# 06-Front_Panel_SFP_2.net
KiCad netlist of a schematic drawn in Altium Designer
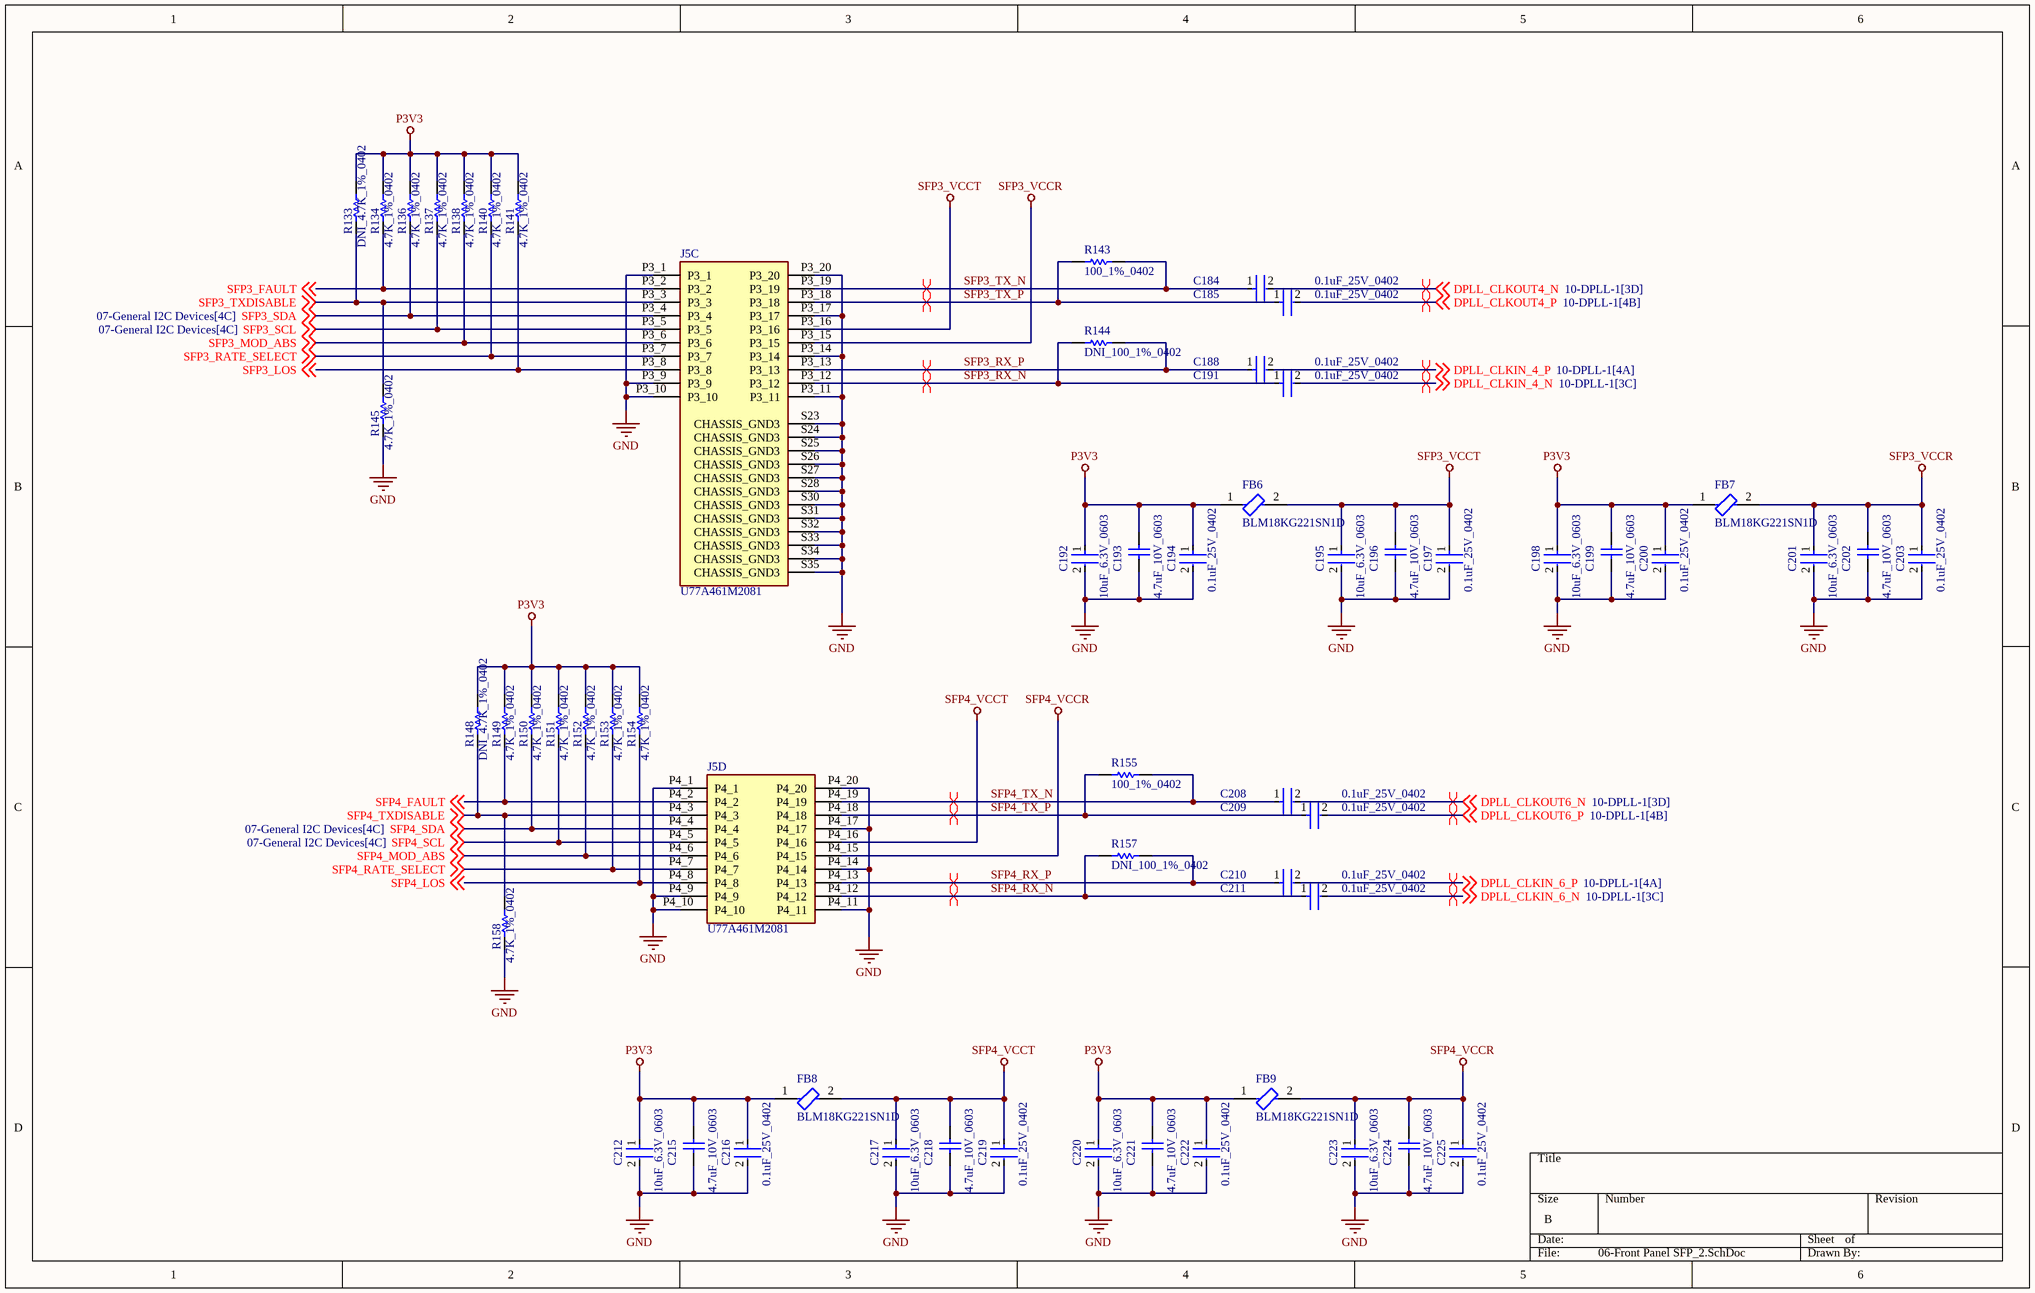
[diagram p0: 06-Front Panel SFP_2.SchDoc]

(export (version "E")
  (design (tool "Eeschema 10.0.6"))
  (components
    (comp (ref "C184")
      (value "0.1uF_25V_0402")
      (footprint "FP-0402-L_1_0_1-W_0_5_0_1-IPC_C")
      (description "General Purpose Ceramic Capacitor, 0402, 100nF, 10%, X7R, 15%, 25V")
      (fields (field (name "VOLTAGE") "25V") (field (name "TOLERANCE") "10%"))
      (libsource (lib "Altium Content Vault") (part "b4654b650e69147ec39a6b967a45e02"))
    )
    (comp (ref "C185")
      (value "0.1uF_25V_0402")
      (footprint "FP-0402-L_1_0_1-W_0_5_0_1-IPC_C")
      (description "General Purpose Ceramic Capacitor, 0402, 100nF, 10%, X7R, 15%, 25V")
      (fields (field (name "VOLTAGE") "25V") (field (name "TOLERANCE") "10%"))
      (libsource (lib "Altium Content Vault") (part "b4654b650e69147ec39a6b967a45e02"))
    )
    (comp (ref "C188")
      (value "0.1uF_25V_0402")
      (footprint "FP-0402-L_1_0_1-W_0_5_0_1-IPC_C")
      (description "General Purpose Ceramic Capacitor, 0402, 100nF, 10%, X7R, 15%, 25V")
      (fields (field (name "VOLTAGE") "25V") (field (name "TOLERANCE") "10%"))
      (libsource (lib "Altium Content Vault") (part "b4654b650e69147ec39a6b967a45e02"))
    )
    (comp (ref "C191")
      (value "0.1uF_25V_0402")
      (footprint "FP-0402-L_1_0_1-W_0_5_0_1-IPC_C")
      (description "General Purpose Ceramic Capacitor, 0402, 100nF, 10%, X7R, 15%, 25V")
      (fields (field (name "VOLTAGE") "25V") (field (name "TOLERANCE") "10%"))
      (libsource (lib "Altium Content Vault") (part "b4654b650e69147ec39a6b967a45e02"))
    )
    (comp (ref "C192")
      (value "10uF_6.3V_0603")
      (footprint "FP-C0603C106M9PACTU-MFG")
      (description "CAP CER 10UF 6.3V X5R 0603")
      (fields
        (field (name "MANUFACTURER PART NUMBER") "C0603C106M9PACTU")
        (field (name "MANUFACTURER") "Kemet")
      )
      (libsource (lib "Altium Content Vault") (part "b4654b650e69147ec39a6b967a45e02"))
    )
    (comp (ref "C193")
      (value "4.7uF_10V_0603")
      (footprint "CAPC1608X87X35NL15T15")
      (fields (field (name "PART NUMBER") "C0603C475K8PACTU") (field (name "MANUFACTURER") "Kemet"))
      (libsource (lib "Altium Content Vault") (part "CAP"))
    )
    (comp (ref "C194")
      (value "0.1uF_25V_0402")
      (footprint "FP-0402-L_1_0_1-W_0_5_0_1-IPC_C")
      (description "General Purpose Ceramic Capacitor, 0402, 100nF, 10%, X7R, 15%, 25V")
      (fields (field (name "VOLTAGE") "25V") (field (name "TOLERANCE") "10%"))
      (libsource (lib "Altium Content Vault") (part "b4654b650e69147ec39a6b967a45e02"))
    )
    (comp (ref "C195")
      (value "10uF_6.3V_0603")
      (footprint "FP-C0603C106M9PACTU-MFG")
      (description "CAP CER 10UF 6.3V X5R 0603")
      (fields
        (field (name "MANUFACTURER PART NUMBER") "C0603C106M9PACTU")
        (field (name "MANUFACTURER") "Kemet")
      )
      (libsource (lib "Altium Content Vault") (part "b4654b650e69147ec39a6b967a45e02"))
    )
    (comp (ref "C196")
      (value "4.7uF_10V_0603")
      (footprint "CAPC1608X87X35NL15T15")
      (fields (field (name "PART NUMBER") "C0603C475K8PACTU") (field (name "MANUFACTURER") "Kemet"))
      (libsource (lib "Altium Content Vault") (part "CAP"))
    )
    (comp (ref "C197")
      (value "0.1uF_25V_0402")
      (footprint "FP-0402-L_1_0_1-W_0_5_0_1-IPC_C")
      (description "General Purpose Ceramic Capacitor, 0402, 100nF, 10%, X7R, 15%, 25V")
      (fields (field (name "VOLTAGE") "25V") (field (name "TOLERANCE") "10%"))
      (libsource (lib "Altium Content Vault") (part "b4654b650e69147ec39a6b967a45e02"))
    )
    (comp (ref "C198")
      (value "10uF_6.3V_0603")
      (footprint "FP-C0603C106M9PACTU-MFG")
      (description "CAP CER 10UF 6.3V X5R 0603")
      (fields
        (field (name "MANUFACTURER PART NUMBER") "C0603C106M9PACTU")
        (field (name "MANUFACTURER") "Kemet")
      )
      (libsource (lib "Altium Content Vault") (part "b4654b650e69147ec39a6b967a45e02"))
    )
    (comp (ref "C199")
      (value "4.7uF_10V_0603")
      (footprint "CAPC1608X87X35NL15T15")
      (fields (field (name "PART NUMBER") "C0603C475K8PACTU") (field (name "MANUFACTURER") "Kemet"))
      (libsource (lib "Altium Content Vault") (part "CAP"))
    )
    (comp (ref "C200")
      (value "0.1uF_25V_0402")
      (footprint "FP-0402-L_1_0_1-W_0_5_0_1-IPC_C")
      (description "General Purpose Ceramic Capacitor, 0402, 100nF, 10%, X7R, 15%, 25V")
      (fields (field (name "VOLTAGE") "25V") (field (name "TOLERANCE") "10%"))
      (libsource (lib "Altium Content Vault") (part "b4654b650e69147ec39a6b967a45e02"))
    )
    (comp (ref "C201")
      (value "10uF_6.3V_0603")
      (footprint "FP-C0603C106M9PACTU-MFG")
      (description "CAP CER 10UF 6.3V X5R 0603")
      (fields
        (field (name "MANUFACTURER PART NUMBER") "C0603C106M9PACTU")
        (field (name "MANUFACTURER") "Kemet")
      )
      (libsource (lib "Altium Content Vault") (part "b4654b650e69147ec39a6b967a45e02"))
    )
    (comp (ref "C202")
      (value "4.7uF_10V_0603")
      (footprint "CAPC1608X87X35NL15T15")
      (fields (field (name "PART NUMBER") "C0603C475K8PACTU") (field (name "MANUFACTURER") "Kemet"))
      (libsource (lib "Altium Content Vault") (part "CAP"))
    )
    (comp (ref "C203")
      (value "0.1uF_25V_0402")
      (footprint "FP-0402-L_1_0_1-W_0_5_0_1-IPC_C")
      (description "General Purpose Ceramic Capacitor, 0402, 100nF, 10%, X7R, 15%, 25V")
      (fields (field (name "VOLTAGE") "25V") (field (name "TOLERANCE") "10%"))
      (libsource (lib "Altium Content Vault") (part "b4654b650e69147ec39a6b967a45e02"))
    )
    (comp (ref "C208")
      (value "0.1uF_25V_0402")
      (footprint "FP-0402-L_1_0_1-W_0_5_0_1-IPC_C")
      (description "General Purpose Ceramic Capacitor, 0402, 100nF, 10%, X7R, 15%, 25V")
      (fields (field (name "VOLTAGE") "25V") (field (name "TOLERANCE") "10%"))
      (libsource (lib "Altium Content Vault") (part "b4654b650e69147ec39a6b967a45e02"))
    )
    (comp (ref "C209")
      (value "0.1uF_25V_0402")
      (footprint "FP-0402-L_1_0_1-W_0_5_0_1-IPC_C")
      (description "General Purpose Ceramic Capacitor, 0402, 100nF, 10%, X7R, 15%, 25V")
      (fields (field (name "VOLTAGE") "25V") (field (name "TOLERANCE") "10%"))
      (libsource (lib "Altium Content Vault") (part "b4654b650e69147ec39a6b967a45e02"))
    )
    (comp (ref "C210")
      (value "0.1uF_25V_0402")
      (footprint "FP-0402-L_1_0_1-W_0_5_0_1-IPC_C")
      (description "General Purpose Ceramic Capacitor, 0402, 100nF, 10%, X7R, 15%, 25V")
      (fields (field (name "VOLTAGE") "25V") (field (name "TOLERANCE") "10%"))
      (libsource (lib "Altium Content Vault") (part "b4654b650e69147ec39a6b967a45e02"))
    )
    (comp (ref "C211")
      (value "0.1uF_25V_0402")
      (footprint "FP-0402-L_1_0_1-W_0_5_0_1-IPC_C")
      (description "General Purpose Ceramic Capacitor, 0402, 100nF, 10%, X7R, 15%, 25V")
      (fields (field (name "VOLTAGE") "25V") (field (name "TOLERANCE") "10%"))
      (libsource (lib "Altium Content Vault") (part "b4654b650e69147ec39a6b967a45e02"))
    )
    (comp (ref "C212")
      (value "10uF_6.3V_0603")
      (footprint "FP-C0603C106M9PACTU-MFG")
      (description "CAP CER 10UF 6.3V X5R 0603")
      (fields
        (field (name "MANUFACTURER PART NUMBER") "C0603C106M9PACTU")
        (field (name "MANUFACTURER") "Kemet")
      )
      (libsource (lib "Altium Content Vault") (part "b4654b650e69147ec39a6b967a45e02"))
    )
    (comp (ref "C215")
      (value "4.7uF_10V_0603")
      (footprint "CAPC1608X87X35NL15T15")
      (fields (field (name "PART NUMBER") "C0603C475K8PACTU") (field (name "MANUFACTURER") "Kemet"))
      (libsource (lib "Altium Content Vault") (part "CAP"))
    )
    (comp (ref "C216")
      (value "0.1uF_25V_0402")
      (footprint "FP-0402-L_1_0_1-W_0_5_0_1-IPC_C")
      (description "General Purpose Ceramic Capacitor, 0402, 100nF, 10%, X7R, 15%, 25V")
      (fields (field (name "VOLTAGE") "25V") (field (name "TOLERANCE") "10%"))
      (libsource (lib "Altium Content Vault") (part "b4654b650e69147ec39a6b967a45e02"))
    )
    (comp (ref "C217")
      (value "10uF_6.3V_0603")
      (footprint "FP-C0603C106M9PACTU-MFG")
      (description "CAP CER 10UF 6.3V X5R 0603")
      (fields
        (field (name "MANUFACTURER PART NUMBER") "C0603C106M9PACTU")
        (field (name "MANUFACTURER") "Kemet")
      )
      (libsource (lib "Altium Content Vault") (part "b4654b650e69147ec39a6b967a45e02"))
    )
    (comp (ref "C218")
      (value "4.7uF_10V_0603")
      (footprint "CAPC1608X87X35NL15T15")
      (fields (field (name "PART NUMBER") "C0603C475K8PACTU") (field (name "MANUFACTURER") "Kemet"))
      (libsource (lib "Altium Content Vault") (part "CAP"))
    )
    (comp (ref "C219")
      (value "0.1uF_25V_0402")
      (footprint "FP-0402-L_1_0_1-W_0_5_0_1-IPC_C")
      (description "General Purpose Ceramic Capacitor, 0402, 100nF, 10%, X7R, 15%, 25V")
      (fields (field (name "VOLTAGE") "25V") (field (name "TOLERANCE") "10%"))
      (libsource (lib "Altium Content Vault") (part "b4654b650e69147ec39a6b967a45e02"))
    )
    (comp (ref "C220")
      (value "10uF_6.3V_0603")
      (footprint "FP-C0603C106M9PACTU-MFG")
      (description "CAP CER 10UF 6.3V X5R 0603")
      (fields
        (field (name "MANUFACTURER PART NUMBER") "C0603C106M9PACTU")
        (field (name "MANUFACTURER") "Kemet")
      )
      (libsource (lib "Altium Content Vault") (part "b4654b650e69147ec39a6b967a45e02"))
    )
    (comp (ref "C221")
      (value "4.7uF_10V_0603")
      (footprint "CAPC1608X87X35NL15T15")
      (fields (field (name "PART NUMBER") "C0603C475K8PACTU") (field (name "MANUFACTURER") "Kemet"))
      (libsource (lib "Altium Content Vault") (part "CAP"))
    )
    (comp (ref "C222")
      (value "0.1uF_25V_0402")
      (footprint "FP-0402-L_1_0_1-W_0_5_0_1-IPC_C")
      (description "General Purpose Ceramic Capacitor, 0402, 100nF, 10%, X7R, 15%, 25V")
      (fields (field (name "VOLTAGE") "25V") (field (name "TOLERANCE") "10%"))
      (libsource (lib "Altium Content Vault") (part "b4654b650e69147ec39a6b967a45e02"))
    )
    (comp (ref "C223")
      (value "10uF_6.3V_0603")
      (footprint "FP-C0603C106M9PACTU-MFG")
      (description "CAP CER 10UF 6.3V X5R 0603")
      (fields
        (field (name "MANUFACTURER PART NUMBER") "C0603C106M9PACTU")
        (field (name "MANUFACTURER") "Kemet")
      )
      (libsource (lib "Altium Content Vault") (part "b4654b650e69147ec39a6b967a45e02"))
    )
    (comp (ref "C224")
      (value "4.7uF_10V_0603")
      (footprint "CAPC1608X87X35NL15T15")
      (fields (field (name "PART NUMBER") "C0603C475K8PACTU") (field (name "MANUFACTURER") "Kemet"))
      (libsource (lib "Altium Content Vault") (part "CAP"))
    )
    (comp (ref "C225")
      (value "0.1uF_25V_0402")
      (footprint "FP-0402-L_1_0_1-W_0_5_0_1-IPC_C")
      (description "General Purpose Ceramic Capacitor, 0402, 100nF, 10%, X7R, 15%, 25V")
      (fields (field (name "VOLTAGE") "25V") (field (name "TOLERANCE") "10%"))
      (libsource (lib "Altium Content Vault") (part "b4654b650e69147ec39a6b967a45e02"))
    )
    (comp (ref "FB6")
      (value "BLM18KG221SN1D")
      (footprint "FP-BLM18-0_15-t0_8-IPC_B")
      (description "Chip Ferrite Bead, 0603, 220Ω @ 100MHz, 0.05Ω, 25%, 2.2A")
      (fields (field (name "TOLERANCE") "25%"))
      (libsource (lib "Altium Content Vault") (part "5f30dd21d616792df468990f7003faa"))
    )
    (comp (ref "FB7")
      (value "BLM18KG221SN1D")
      (footprint "FP-BLM18-0_15-t0_8-IPC_B")
      (description "Chip Ferrite Bead, 0603, 220Ω @ 100MHz, 0.05Ω, 25%, 2.2A")
      (fields (field (name "TOLERANCE") "25%"))
      (libsource (lib "Altium Content Vault") (part "5f30dd21d616792df468990f7003faa"))
    )
    (comp (ref "FB8")
      (value "BLM18KG221SN1D")
      (footprint "FP-BLM18-0_15-t0_8-IPC_B")
      (description "Chip Ferrite Bead, 0603, 220Ω @ 100MHz, 0.05Ω, 25%, 2.2A")
      (fields (field (name "TOLERANCE") "25%"))
      (libsource (lib "Altium Content Vault") (part "5f30dd21d616792df468990f7003faa"))
    )
    (comp (ref "FB9")
      (value "BLM18KG221SN1D")
      (footprint "FP-BLM18-0_15-t0_8-IPC_B")
      (description "Chip Ferrite Bead, 0603, 220Ω @ 100MHz, 0.05Ω, 25%, 2.2A")
      (fields (field (name "TOLERANCE") "25%"))
      (libsource (lib "Altium Content Vault") (part "5f30dd21d616792df468990f7003faa"))
    )
    (comp (ref "J5")
      (value "U77A461M2081")
      (footprint "AMPHENOL_U77A461M2081")
      (fields (field (name "MF") "AMPHENOL ICC / FCI"))
      (libsource (lib "U77A461M2081") (part "U77A461M2081"))
    )
    (comp (ref "R133")
      (value "DNI_4.7K_1%_0402")
      (footprint "RESC1005X40X25NL10T10")
      (fields (field (name "MANUFACTURER") "Bourns") (field (name "PART NUMBER") "CR0402-FX-4701GLF"))
      (libsource (lib "Altium Content Vault") (part "RES"))
    )
    (comp (ref "R134")
      (value "4.7K_1%_0402")
      (footprint "RESC1005X40X25NL10T10")
      (fields (field (name "MANUFACTURER") "Bourns") (field (name "PART NUMBER") "CR0402-FX-4701GLF"))
      (libsource (lib "Altium Content Vault") (part "RES"))
    )
    (comp (ref "R136")
      (value "4.7K_1%_0402")
      (footprint "RESC1005X40X25NL10T10")
      (fields (field (name "MANUFACTURER") "Bourns") (field (name "PART NUMBER") "CR0402-FX-4701GLF"))
      (libsource (lib "Altium Content Vault") (part "RES"))
    )
    (comp (ref "R137")
      (value "4.7K_1%_0402")
      (footprint "RESC1005X40X25NL10T10")
      (fields (field (name "MANUFACTURER") "Bourns") (field (name "PART NUMBER") "CR0402-FX-4701GLF"))
      (libsource (lib "Altium Content Vault") (part "RES"))
    )
    (comp (ref "R138")
      (value "4.7K_1%_0402")
      (footprint "RESC1005X40X25NL10T10")
      (fields (field (name "MANUFACTURER") "Bourns") (field (name "PART NUMBER") "CR0402-FX-4701GLF"))
      (libsource (lib "Altium Content Vault") (part "RES"))
    )
    (comp (ref "R140")
      (value "4.7K_1%_0402")
      (footprint "RESC1005X40X25NL10T10")
      (fields (field (name "MANUFACTURER") "Bourns") (field (name "PART NUMBER") "CR0402-FX-4701GLF"))
      (libsource (lib "Altium Content Vault") (part "RES"))
    )
    (comp (ref "R141")
      (value "4.7K_1%_0402")
      (footprint "RESC1005X40X25NL10T10")
      (fields (field (name "MANUFACTURER") "Bourns") (field (name "PART NUMBER") "CR0402-FX-4701GLF"))
      (libsource (lib "Altium Content Vault") (part "RES"))
    )
    (comp (ref "R143")
      (value "100_1%_0402")
      (footprint "RESC1005X40X25NL05T10")
      (fields (field (name "MANUFACTURER") "Yageo") (field (name "PART NUMBER") "RC0402FR-13100RL"))
      (libsource (lib "Altium Content Vault") (part "RES"))
    )
    (comp (ref "R144")
      (value "DNI_100_1%_0402")
      (footprint "RESC1005X40X25NL05T10")
      (fields (field (name "MANUFACTURER") "Yageo") (field (name "PART NUMBER") "RC0402FR-13100RL"))
      (libsource (lib "Altium Content Vault") (part "RES"))
    )
    (comp (ref "R145")
      (value "4.7K_1%_0402")
      (footprint "RESC1005X40X25NL10T10")
      (fields (field (name "MANUFACTURER") "Bourns") (field (name "PART NUMBER") "CR0402-FX-4701GLF"))
      (libsource (lib "Altium Content Vault") (part "RES"))
    )
    (comp (ref "R148")
      (value "DNI_4.7K_1%_0402")
      (footprint "RESC1005X40X25NL10T10")
      (fields (field (name "MANUFACTURER") "Bourns") (field (name "PART NUMBER") "CR0402-FX-4701GLF"))
      (libsource (lib "Altium Content Vault") (part "RES"))
    )
    (comp (ref "R149")
      (value "4.7K_1%_0402")
      (footprint "RESC1005X40X25NL10T10")
      (fields (field (name "MANUFACTURER") "Bourns") (field (name "PART NUMBER") "CR0402-FX-4701GLF"))
      (libsource (lib "Altium Content Vault") (part "RES"))
    )
    (comp (ref "R150")
      (value "4.7K_1%_0402")
      (footprint "RESC1005X40X25NL10T10")
      (fields (field (name "MANUFACTURER") "Bourns") (field (name "PART NUMBER") "CR0402-FX-4701GLF"))
      (libsource (lib "Altium Content Vault") (part "RES"))
    )
    (comp (ref "R151")
      (value "4.7K_1%_0402")
      (footprint "RESC1005X40X25NL10T10")
      (fields (field (name "MANUFACTURER") "Bourns") (field (name "PART NUMBER") "CR0402-FX-4701GLF"))
      (libsource (lib "Altium Content Vault") (part "RES"))
    )
    (comp (ref "R152")
      (value "4.7K_1%_0402")
      (footprint "RESC1005X40X25NL10T10")
      (fields (field (name "MANUFACTURER") "Bourns") (field (name "PART NUMBER") "CR0402-FX-4701GLF"))
      (libsource (lib "Altium Content Vault") (part "RES"))
    )
    (comp (ref "R153")
      (value "4.7K_1%_0402")
      (footprint "RESC1005X40X25NL10T10")
      (fields (field (name "MANUFACTURER") "Bourns") (field (name "PART NUMBER") "CR0402-FX-4701GLF"))
      (libsource (lib "Altium Content Vault") (part "RES"))
    )
    (comp (ref "R154")
      (value "4.7K_1%_0402")
      (footprint "RESC1005X40X25NL10T10")
      (fields (field (name "MANUFACTURER") "Bourns") (field (name "PART NUMBER") "CR0402-FX-4701GLF"))
      (libsource (lib "Altium Content Vault") (part "RES"))
    )
    (comp (ref "R155")
      (value "100_1%_0402")
      (footprint "RESC1005X40X25NL05T10")
      (fields (field (name "MANUFACTURER") "Yageo") (field (name "PART NUMBER") "RC0402FR-13100RL"))
      (libsource (lib "Altium Content Vault") (part "RES"))
    )
    (comp (ref "R157")
      (value "DNI_100_1%_0402")
      (footprint "RESC1005X40X25NL05T10")
      (fields (field (name "MANUFACTURER") "Yageo") (field (name "PART NUMBER") "RC0402FR-13100RL"))
      (libsource (lib "Altium Content Vault") (part "RES"))
    )
    (comp (ref "R158")
      (value "4.7K_1%_0402")
      (footprint "RESC1005X40X25NL10T10")
      (fields (field (name "MANUFACTURER") "Bourns") (field (name "PART NUMBER") "CR0402-FX-4701GLF"))
      (libsource (lib "Altium Content Vault") (part "RES"))
    )
  )
  (nets
    (net (code "1") (name "/SFP3_RX_N") (class "Default")
      (node (ref "C191") (pin "1") (pinfunction "1_1") (pintype "passive"))
      (node (ref "J5") (pin "P3_12") (pinfunction "P3_12_P3_12") (pintype "passive"))
      (node (ref "R144") (pin "1") (pinfunction "1_1") (pintype "passive"))
    )
    (net (code "2") (name "/SFP3_RX_P") (class "Default")
      (node (ref "C188") (pin "1") (pinfunction "1_1") (pintype "passive"))
      (node (ref "J5") (pin "P3_13") (pinfunction "P3_13_P3_13") (pintype "passive"))
      (node (ref "R144") (pin "2") (pinfunction "2_2") (pintype "passive"))
    )
    (net (code "3") (name "/SFP3_TX_N") (class "Default")
      (node (ref "C184") (pin "1") (pinfunction "1_1") (pintype "passive"))
      (node (ref "J5") (pin "P3_19") (pinfunction "P3_19_P3_19") (pintype "passive"))
      (node (ref "R143") (pin "2") (pinfunction "2_2") (pintype "passive"))
    )
    (net (code "4") (name "/SFP3_TX_P") (class "Default")
      (node (ref "C185") (pin "1") (pinfunction "1_1") (pintype "passive"))
      (node (ref "J5") (pin "P3_18") (pinfunction "P3_18_P3_18") (pintype "passive"))
      (node (ref "R143") (pin "1") (pinfunction "1_1") (pintype "passive"))
    )
    (net (code "5") (name "/SFP4_RX_N") (class "Default")
      (node (ref "C211") (pin "1") (pinfunction "1_1") (pintype "passive"))
      (node (ref "J5") (pin "P4_12") (pinfunction "P4_12_P4_12") (pintype "passive"))
      (node (ref "R157") (pin "1") (pinfunction "1_1") (pintype "passive"))
    )
    (net (code "6") (name "/SFP4_RX_P") (class "Default")
      (node (ref "C210") (pin "1") (pinfunction "1_1") (pintype "passive"))
      (node (ref "J5") (pin "P4_13") (pinfunction "P4_13_P4_13") (pintype "passive"))
      (node (ref "R157") (pin "2") (pinfunction "2_2") (pintype "passive"))
    )
    (net (code "7") (name "/SFP4_TX_N") (class "Default")
      (node (ref "C208") (pin "1") (pinfunction "1_1") (pintype "passive"))
      (node (ref "J5") (pin "P4_19") (pinfunction "P4_19_P4_19") (pintype "passive"))
      (node (ref "R155") (pin "2") (pinfunction "2_2") (pintype "passive"))
    )
    (net (code "8") (name "/SFP4_TX_P") (class "Default")
      (node (ref "C209") (pin "1") (pinfunction "1_1") (pintype "passive"))
      (node (ref "J5") (pin "P4_18") (pinfunction "P4_18_P4_18") (pintype "passive"))
      (node (ref "R155") (pin "1") (pinfunction "1_1") (pintype "passive"))
    )
    (net (code "9") (name "DPLL_CLKIN_4_N") (class "Default")
      (node (ref "C191") (pin "2") (pinfunction "2_2") (pintype "passive"))
    )
    (net (code "10") (name "DPLL_CLKIN_4_P") (class "Default")
      (node (ref "C188") (pin "2") (pinfunction "2_2") (pintype "passive"))
    )
    (net (code "11") (name "DPLL_CLKIN_6_N") (class "Default")
      (node (ref "C211") (pin "2") (pinfunction "2_2") (pintype "passive"))
    )
    (net (code "12") (name "DPLL_CLKIN_6_P") (class "Default")
      (node (ref "C210") (pin "2") (pinfunction "2_2") (pintype "passive"))
    )
    (net (code "13") (name "DPLL_CLKOUT4_N") (class "Default")
      (node (ref "C184") (pin "2") (pinfunction "2_2") (pintype "passive"))
    )
    (net (code "14") (name "DPLL_CLKOUT4_P") (class "Default")
      (node (ref "C185") (pin "2") (pinfunction "2_2") (pintype "passive"))
    )
    (net (code "15") (name "DPLL_CLKOUT6_N") (class "Default")
      (node (ref "C208") (pin "2") (pinfunction "2_2") (pintype "passive"))
    )
    (net (code "16") (name "DPLL_CLKOUT6_P") (class "Default")
      (node (ref "C209") (pin "2") (pinfunction "2_2") (pintype "passive"))
    )
    (net (code "17") (name "GND") (class "Default")
      (node (ref "C192") (pin "2") (pinfunction "2_2") (pintype "passive"))
      (node (ref "C193") (pin "1") (pinfunction "1_1") (pintype "passive"))
      (node (ref "C194") (pin "2") (pinfunction "2_2") (pintype "passive"))
      (node (ref "C195") (pin "2") (pinfunction "2_2") (pintype "passive"))
      (node (ref "C196") (pin "1") (pinfunction "1_1") (pintype "passive"))
      (node (ref "C197") (pin "2") (pinfunction "2_2") (pintype "passive"))
      (node (ref "C198") (pin "2") (pinfunction "2_2") (pintype "passive"))
      (node (ref "C199") (pin "1") (pinfunction "1_1") (pintype "passive"))
      (node (ref "C200") (pin "2") (pinfunction "2_2") (pintype "passive"))
      (node (ref "C201") (pin "2") (pinfunction "2_2") (pintype "passive"))
      (node (ref "C202") (pin "1") (pinfunction "1_1") (pintype "passive"))
      (node (ref "C203") (pin "2") (pinfunction "2_2") (pintype "passive"))
      (node (ref "C212") (pin "2") (pinfunction "2_2") (pintype "passive"))
      (node (ref "C215") (pin "1") (pinfunction "1_1") (pintype "passive"))
      (node (ref "C216") (pin "2") (pinfunction "2_2") (pintype "passive"))
      (node (ref "C217") (pin "2") (pinfunction "2_2") (pintype "passive"))
      (node (ref "C218") (pin "1") (pinfunction "1_1") (pintype "passive"))
      (node (ref "C219") (pin "2") (pinfunction "2_2") (pintype "passive"))
      (node (ref "C220") (pin "2") (pinfunction "2_2") (pintype "passive"))
      (node (ref "C221") (pin "1") (pinfunction "1_1") (pintype "passive"))
      (node (ref "C222") (pin "2") (pinfunction "2_2") (pintype "passive"))
      (node (ref "C223") (pin "2") (pinfunction "2_2") (pintype "passive"))
      (node (ref "C224") (pin "1") (pinfunction "1_1") (pintype "passive"))
      (node (ref "C225") (pin "2") (pinfunction "2_2") (pintype "passive"))
      (node (ref "J5") (pin "P3_1") (pinfunction "P3_1_P3_1") (pintype "passive"))
      (node (ref "J5") (pin "P3_10") (pinfunction "P3_10_P3_10") (pintype "passive"))
      (node (ref "J5") (pin "P3_11") (pinfunction "P3_11_P3_11") (pintype "passive"))
      (node (ref "J5") (pin "P3_14") (pinfunction "P3_14_P3_14") (pintype "passive"))
      (node (ref "J5") (pin "P3_17") (pinfunction "P3_17_P3_17") (pintype "passive"))
      (node (ref "J5") (pin "P3_20") (pinfunction "P3_20_P3_20") (pintype "passive"))
      (node (ref "J5") (pin "P3_9") (pinfunction "P3_9_P3_9") (pintype "passive"))
      (node (ref "J5") (pin "P4_1") (pinfunction "P4_1_P4_1") (pintype "passive"))
      (node (ref "J5") (pin "P4_10") (pinfunction "P4_10_P4_10") (pintype "passive"))
      (node (ref "J5") (pin "P4_11") (pinfunction "P4_11_P4_11") (pintype "passive"))
      (node (ref "J5") (pin "P4_14") (pinfunction "P4_14_P4_14") (pintype "passive"))
      (node (ref "J5") (pin "P4_17") (pinfunction "P4_17_P4_17") (pintype "passive"))
      (node (ref "J5") (pin "P4_20") (pinfunction "P4_20_P4_20") (pintype "passive"))
      (node (ref "J5") (pin "P4_9") (pinfunction "P4_9_P4_9") (pintype "passive"))
      (node (ref "J5") (pin "S23") (pinfunction "CHASSIS_GND3_S23") (pintype "passive"))
      (node (ref "J5") (pin "S24") (pinfunction "CHASSIS_GND3_S24") (pintype "passive"))
      (node (ref "J5") (pin "S25") (pinfunction "CHASSIS_GND3_S25") (pintype "passive"))
      (node (ref "J5") (pin "S26") (pinfunction "CHASSIS_GND3_S26") (pintype "passive"))
      (node (ref "J5") (pin "S27") (pinfunction "CHASSIS_GND3_S27") (pintype "passive"))
      (node (ref "J5") (pin "S28") (pinfunction "CHASSIS_GND3_S28") (pintype "passive"))
      (node (ref "J5") (pin "S30") (pinfunction "CHASSIS_GND3_S30") (pintype "passive"))
      (node (ref "J5") (pin "S31") (pinfunction "CHASSIS_GND3_S31") (pintype "passive"))
      (node (ref "J5") (pin "S32") (pinfunction "CHASSIS_GND3_S32") (pintype "passive"))
      (node (ref "J5") (pin "S33") (pinfunction "CHASSIS_GND3_S33") (pintype "passive"))
      (node (ref "J5") (pin "S34") (pinfunction "CHASSIS_GND3_S34") (pintype "passive"))
      (node (ref "J5") (pin "S35") (pinfunction "CHASSIS_GND3_S35") (pintype "passive"))
      (node (ref "R145") (pin "2") (pinfunction "2_2") (pintype "passive"))
      (node (ref "R158") (pin "2") (pinfunction "2_2") (pintype "passive"))
    )
    (net (code "18") (name "P3V3") (class "Default")
      (node (ref "C192") (pin "1") (pinfunction "1_1") (pintype "passive"))
      (node (ref "C193") (pin "2") (pinfunction "2_2") (pintype "passive"))
      (node (ref "C194") (pin "1") (pinfunction "1_1") (pintype "passive"))
      (node (ref "C198") (pin "1") (pinfunction "1_1") (pintype "passive"))
      (node (ref "C199") (pin "2") (pinfunction "2_2") (pintype "passive"))
      (node (ref "C200") (pin "1") (pinfunction "1_1") (pintype "passive"))
      (node (ref "C212") (pin "1") (pinfunction "1_1") (pintype "passive"))
      (node (ref "C215") (pin "2") (pinfunction "2_2") (pintype "passive"))
      (node (ref "C216") (pin "1") (pinfunction "1_1") (pintype "passive"))
      (node (ref "C220") (pin "1") (pinfunction "1_1") (pintype "passive"))
      (node (ref "C221") (pin "2") (pinfunction "2_2") (pintype "passive"))
      (node (ref "C222") (pin "1") (pinfunction "1_1") (pintype "passive"))
      (node (ref "FB6") (pin "1") (pinfunction "1_1") (pintype "passive"))
      (node (ref "FB7") (pin "1") (pinfunction "1_1") (pintype "passive"))
      (node (ref "FB8") (pin "1") (pinfunction "1_1") (pintype "passive"))
      (node (ref "FB9") (pin "1") (pinfunction "1_1") (pintype "passive"))
      (node (ref "R133") (pin "1") (pinfunction "1_1") (pintype "passive"))
      (node (ref "R134") (pin "1") (pinfunction "1_1") (pintype "passive"))
      (node (ref "R136") (pin "1") (pinfunction "1_1") (pintype "passive"))
      (node (ref "R137") (pin "1") (pinfunction "1_1") (pintype "passive"))
      (node (ref "R138") (pin "1") (pinfunction "1_1") (pintype "passive"))
      (node (ref "R140") (pin "1") (pinfunction "1_1") (pintype "passive"))
      (node (ref "R141") (pin "1") (pinfunction "1_1") (pintype "passive"))
      (node (ref "R148") (pin "1") (pinfunction "1_1") (pintype "passive"))
      (node (ref "R149") (pin "1") (pinfunction "1_1") (pintype "passive"))
      (node (ref "R150") (pin "1") (pinfunction "1_1") (pintype "passive"))
      (node (ref "R151") (pin "1") (pinfunction "1_1") (pintype "passive"))
      (node (ref "R152") (pin "1") (pinfunction "1_1") (pintype "passive"))
      (node (ref "R153") (pin "1") (pinfunction "1_1") (pintype "passive"))
      (node (ref "R154") (pin "1") (pinfunction "1_1") (pintype "passive"))
    )
    (net (code "19") (name "SFP3_FAULT") (class "Default")
      (node (ref "J5") (pin "P3_2") (pinfunction "P3_2_P3_2") (pintype "passive"))
      (node (ref "R134") (pin "2") (pinfunction "2_2") (pintype "passive"))
    )
    (net (code "20") (name "SFP3_LOS") (class "Default")
      (node (ref "J5") (pin "P3_8") (pinfunction "P3_8_P3_8") (pintype "passive"))
      (node (ref "R141") (pin "2") (pinfunction "2_2") (pintype "passive"))
    )
    (net (code "21") (name "SFP3_MOD_ABS") (class "Default")
      (node (ref "J5") (pin "P3_6") (pinfunction "P3_6_P3_6") (pintype "passive"))
      (node (ref "R138") (pin "2") (pinfunction "2_2") (pintype "passive"))
    )
    (net (code "22") (name "SFP3_RATE_SELECT") (class "Default")
      (node (ref "J5") (pin "P3_7") (pinfunction "P3_7_P3_7") (pintype "passive"))
      (node (ref "R140") (pin "2") (pinfunction "2_2") (pintype "passive"))
    )
    (net (code "23") (name "SFP3_SCL") (class "Default")
      (node (ref "J5") (pin "P3_5") (pinfunction "P3_5_P3_5") (pintype "passive"))
      (node (ref "R137") (pin "2") (pinfunction "2_2") (pintype "passive"))
    )
    (net (code "24") (name "SFP3_SDA") (class "Default")
      (node (ref "J5") (pin "P3_4") (pinfunction "P3_4_P3_4") (pintype "passive"))
      (node (ref "R136") (pin "2") (pinfunction "2_2") (pintype "passive"))
    )
    (net (code "25") (name "SFP3_TXDISABLE") (class "Default")
      (node (ref "J5") (pin "P3_3") (pinfunction "P3_3_P3_3") (pintype "passive"))
      (node (ref "R133") (pin "2") (pinfunction "2_2") (pintype "passive"))
      (node (ref "R145") (pin "1") (pinfunction "1_1") (pintype "passive"))
    )
    (net (code "26") (name "SFP3_VCCR") (class "Default")
      (node (ref "C201") (pin "1") (pinfunction "1_1") (pintype "passive"))
      (node (ref "C202") (pin "2") (pinfunction "2_2") (pintype "passive"))
      (node (ref "C203") (pin "1") (pinfunction "1_1") (pintype "passive"))
      (node (ref "FB7") (pin "2") (pinfunction "2_2") (pintype "passive"))
      (node (ref "J5") (pin "P3_15") (pinfunction "P3_15_P3_15") (pintype "passive"))
    )
    (net (code "27") (name "SFP3_VCCT") (class "Default")
      (node (ref "C195") (pin "1") (pinfunction "1_1") (pintype "passive"))
      (node (ref "C196") (pin "2") (pinfunction "2_2") (pintype "passive"))
      (node (ref "C197") (pin "1") (pinfunction "1_1") (pintype "passive"))
      (node (ref "FB6") (pin "2") (pinfunction "2_2") (pintype "passive"))
      (node (ref "J5") (pin "P3_16") (pinfunction "P3_16_P3_16") (pintype "passive"))
    )
    (net (code "28") (name "SFP4_FAULT") (class "Default")
      (node (ref "J5") (pin "P4_2") (pinfunction "P4_2_P4_2") (pintype "passive"))
      (node (ref "R149") (pin "2") (pinfunction "2_2") (pintype "passive"))
    )
    (net (code "29") (name "SFP4_LOS") (class "Default")
      (node (ref "J5") (pin "P4_8") (pinfunction "P4_8_P4_8") (pintype "passive"))
      (node (ref "R154") (pin "2") (pinfunction "2_2") (pintype "passive"))
    )
    (net (code "30") (name "SFP4_MOD_ABS") (class "Default")
      (node (ref "J5") (pin "P4_6") (pinfunction "P4_6_P4_6") (pintype "passive"))
      (node (ref "R152") (pin "2") (pinfunction "2_2") (pintype "passive"))
    )
    (net (code "31") (name "SFP4_RATE_SELECT") (class "Default")
      (node (ref "J5") (pin "P4_7") (pinfunction "P4_7_P4_7") (pintype "passive"))
      (node (ref "R153") (pin "2") (pinfunction "2_2") (pintype "passive"))
    )
    (net (code "32") (name "SFP4_SCL") (class "Default")
      (node (ref "J5") (pin "P4_5") (pinfunction "P4_5_P4_5") (pintype "passive"))
      (node (ref "R151") (pin "2") (pinfunction "2_2") (pintype "passive"))
    )
    (net (code "33") (name "SFP4_SDA") (class "Default")
      (node (ref "J5") (pin "P4_4") (pinfunction "P4_4_P4_4") (pintype "passive"))
      (node (ref "R150") (pin "2") (pinfunction "2_2") (pintype "passive"))
    )
    (net (code "34") (name "SFP4_TXDISABLE") (class "Default")
      (node (ref "J5") (pin "P4_3") (pinfunction "P4_3_P4_3") (pintype "passive"))
      (node (ref "R148") (pin "2") (pinfunction "2_2") (pintype "passive"))
      (node (ref "R158") (pin "1") (pinfunction "1_1") (pintype "passive"))
    )
    (net (code "35") (name "SFP4_VCCR") (class "Default")
      (node (ref "C223") (pin "1") (pinfunction "1_1") (pintype "passive"))
      (node (ref "C224") (pin "2") (pinfunction "2_2") (pintype "passive"))
      (node (ref "C225") (pin "1") (pinfunction "1_1") (pintype "passive"))
      (node (ref "FB9") (pin "2") (pinfunction "2_2") (pintype "passive"))
      (node (ref "J5") (pin "P4_15") (pinfunction "P4_15_P4_15") (pintype "passive"))
    )
    (net (code "36") (name "SFP4_VCCT") (class "Default")
      (node (ref "C217") (pin "1") (pinfunction "1_1") (pintype "passive"))
      (node (ref "C218") (pin "2") (pinfunction "2_2") (pintype "passive"))
      (node (ref "C219") (pin "1") (pinfunction "1_1") (pintype "passive"))
      (node (ref "FB8") (pin "2") (pinfunction "2_2") (pintype "passive"))
      (node (ref "J5") (pin "P4_16") (pinfunction "P4_16_P4_16") (pintype "passive"))
    )
  )
)
